# 2KbeaconDetectorV1_0.net
KiCad netlist of a schematic drawn in EAGLE
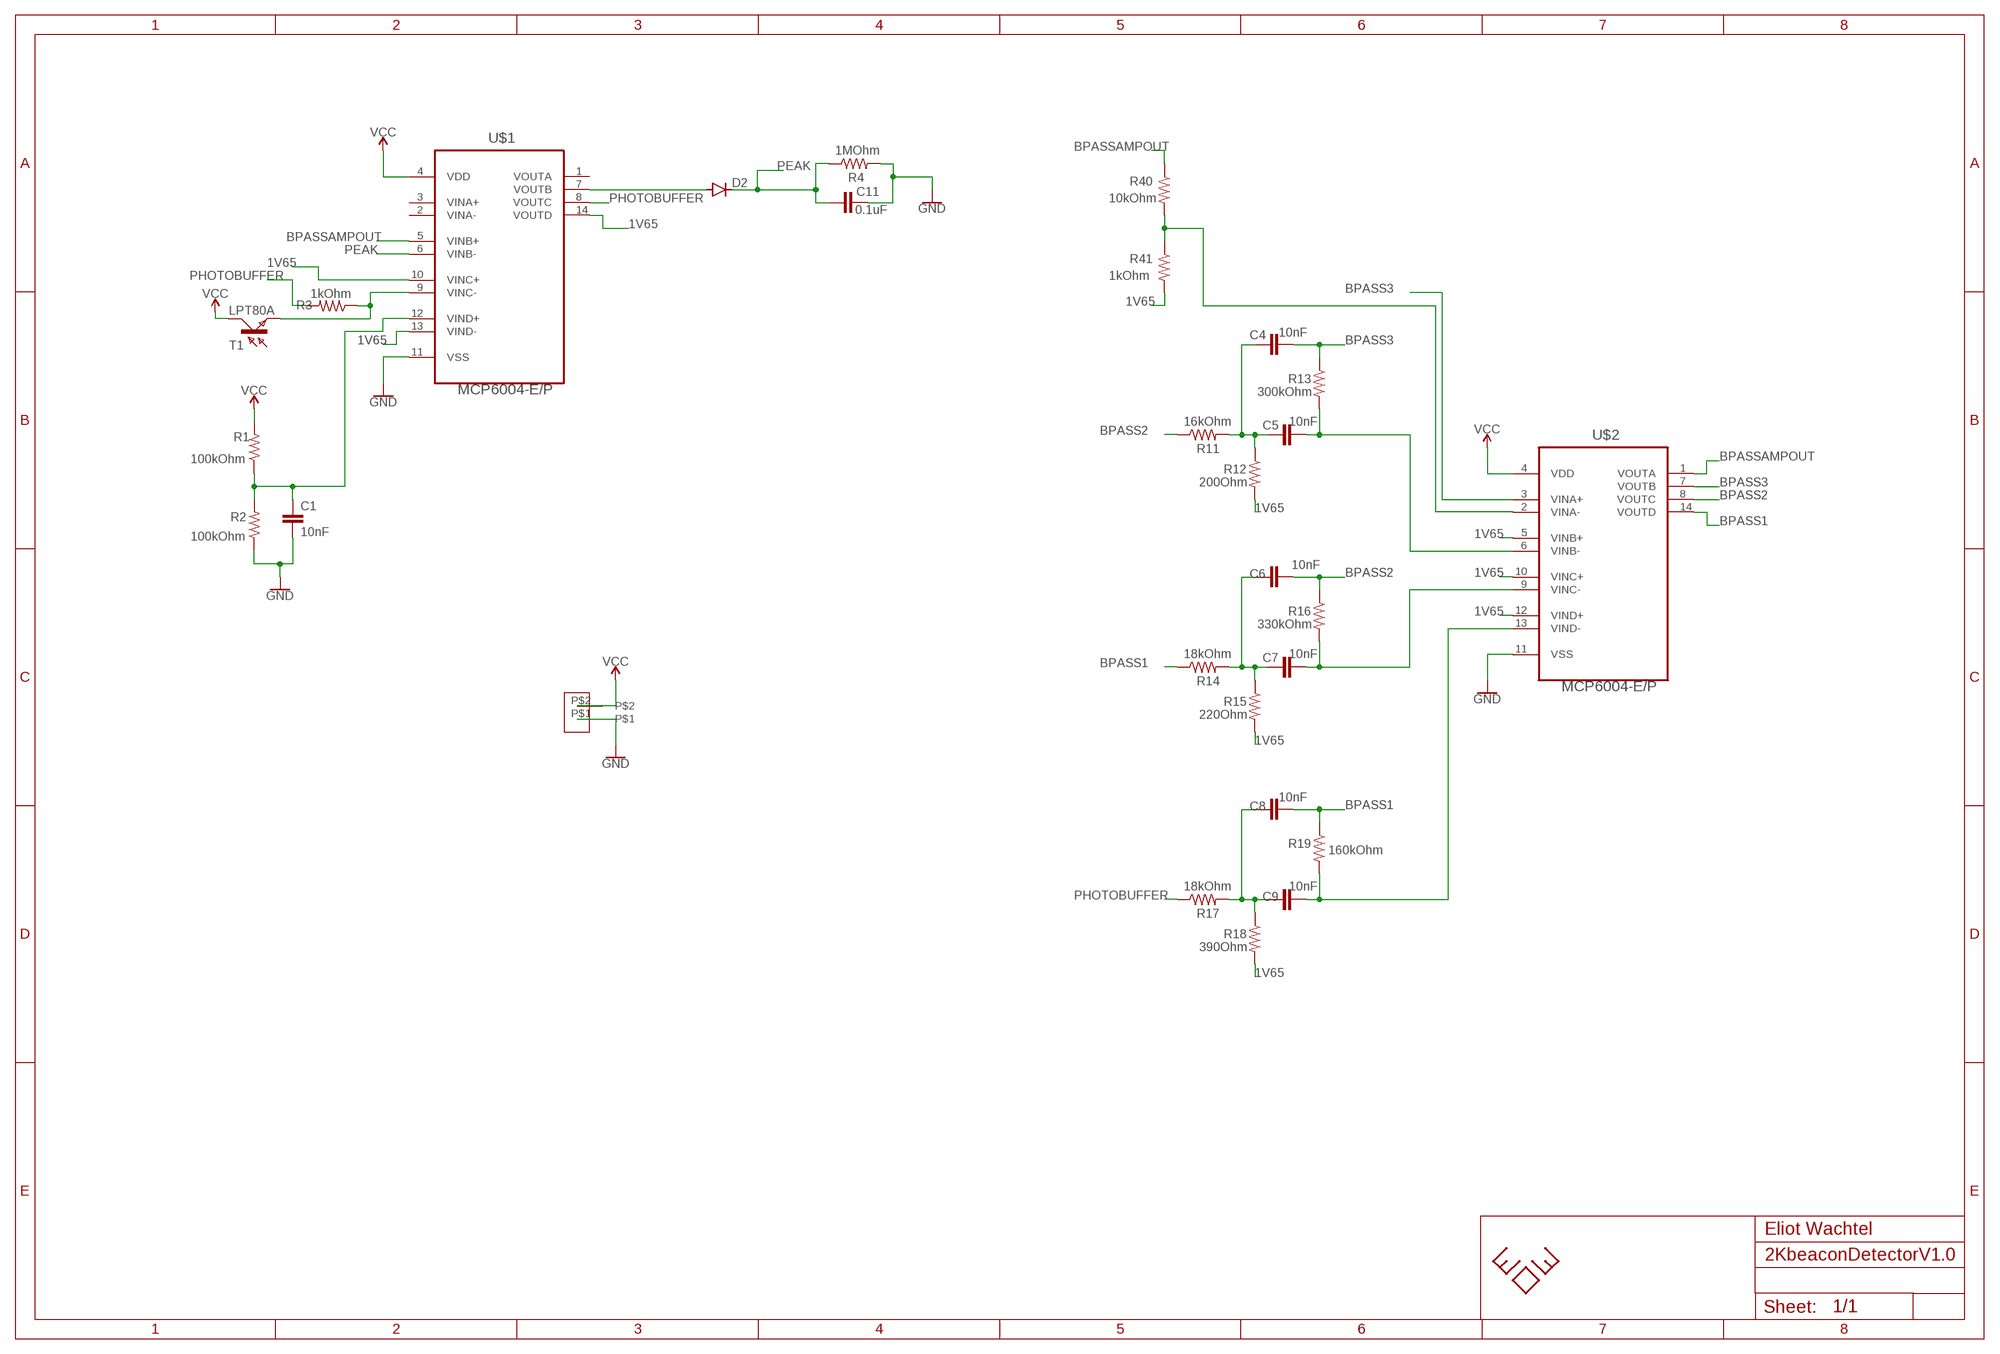
[diagram p0: schematic, sheet 1]

(export (version "E")
  (design (tool "Eeschema 10.0.6"))
  (components
    (comp (ref "C1")
      (value "10nF")
      (footprint "eagle-import:C5B2.5")
      (libsource (lib "eagle-import") (part "C5/2.5"))
    )
    (comp (ref "C4")
      (value "10nF")
      (footprint "eagle-import:C5B2.5")
      (libsource (lib "eagle-import") (part "C5/2.5"))
    )
    (comp (ref "C5")
      (value "10nF")
      (footprint "eagle-import:C5B2.5")
      (libsource (lib "eagle-import") (part "C5/2.5"))
    )
    (comp (ref "C6")
      (value "10nF")
      (footprint "eagle-import:C5B2.5")
      (libsource (lib "eagle-import") (part "C5/2.5"))
    )
    (comp (ref "C7")
      (value "10nF")
      (footprint "eagle-import:C5B2.5")
      (libsource (lib "eagle-import") (part "C5/2.5"))
    )
    (comp (ref "C8")
      (value "10nF")
      (footprint "eagle-import:C5B2.5")
      (libsource (lib "eagle-import") (part "C5/2.5"))
    )
    (comp (ref "C9")
      (value "10nF")
      (footprint "eagle-import:C5B2.5")
      (libsource (lib "eagle-import") (part "C5/2.5"))
    )
    (comp (ref "C11")
      (value "0.1uF")
      (footprint "eagle-import:C5B2.5")
      (libsource (lib "eagle-import") (part "C5/2.5"))
    )
    (comp (ref "D2")
      (value "DIODE-D-7.5")
      (footprint "eagle-import:D-7.5")
      (libsource (lib "eagle-import") (part "DIODE-D-7.5"))
    )
    (comp (ref "R1")
      (value "100kOhm")
      (footprint "eagle-import:0207_5V")
      (libsource (lib "eagle-import") (part "R-US_0207/5V"))
    )
    (comp (ref "R2")
      (value "100kOhm")
      (footprint "eagle-import:0207_5V")
      (libsource (lib "eagle-import") (part "R-US_0207/5V"))
    )
    (comp (ref "R3")
      (value "1kOhm")
      (footprint "eagle-import:0204V")
      (libsource (lib "eagle-import") (part "R-US_0204/2V"))
    )
    (comp (ref "R4")
      (value "1MOhm")
      (footprint "eagle-import:0204_5")
      (libsource (lib "eagle-import") (part "R-US_0204/5"))
    )
    (comp (ref "R11")
      (value "16kOhm")
      (footprint "eagle-import:0204V")
      (libsource (lib "eagle-import") (part "R-US_0204/2V"))
    )
    (comp (ref "R12")
      (value "200Ohm")
      (footprint "eagle-import:0204_7")
      (libsource (lib "eagle-import") (part "R-US_0204/7"))
    )
    (comp (ref "R13")
      (value "300kOhm")
      (footprint "eagle-import:0204V")
      (libsource (lib "eagle-import") (part "R-US_0204/2V"))
    )
    (comp (ref "R14")
      (value "18kOhm")
      (footprint "eagle-import:0204V")
      (libsource (lib "eagle-import") (part "R-US_0204/2V"))
    )
    (comp (ref "R15")
      (value "220Ohm")
      (footprint "eagle-import:0204_7")
      (libsource (lib "eagle-import") (part "R-US_0204/7"))
    )
    (comp (ref "R16")
      (value "330kOhm")
      (footprint "eagle-import:0204V")
      (libsource (lib "eagle-import") (part "R-US_0204/2V"))
    )
    (comp (ref "R17")
      (value "18kOhm")
      (footprint "eagle-import:0204V")
      (libsource (lib "eagle-import") (part "R-US_0204/2V"))
    )
    (comp (ref "R18")
      (value "390Ohm")
      (footprint "eagle-import:0204_7")
      (libsource (lib "eagle-import") (part "R-US_0204/7"))
    )
    (comp (ref "R19")
      (value "160kOhm")
      (footprint "eagle-import:0204V")
      (libsource (lib "eagle-import") (part "R-US_0204/2V"))
    )
    (comp (ref "R40")
      (value "10kOhm")
      (footprint "eagle-import:0204_7")
      (libsource (lib "eagle-import") (part "R-US_0204/7"))
    )
    (comp (ref "R41")
      (value "1kOhm")
      (footprint "eagle-import:0204_7")
      (libsource (lib "eagle-import") (part "R-US_0204/7"))
    )
    (comp (ref "T1")
      (value "LPT80A")
      (footprint "eagle-import:LPT80A")
      (libsource (lib "eagle-import") (part "LPT80A"))
    )
    (comp (ref "U$1")
      (value "MCP6004-E/P")
      (footprint "eagle-import:DIP254P762X533-14")
      (fields
        (field (name "DIGI-KEY_PART_NUMBER") "MCP6004-E/P-ND")
        (field (name "MF") "Microchip Technology")
      )
      (libsource (lib "eagle-import") (part "MCP6004-E/P"))
    )
    (comp (ref "U$2")
      (value "MCP6004-E/P")
      (footprint "eagle-import:DIP254P762X533-14")
      (fields
        (field (name "DIGI-KEY_PART_NUMBER") "MCP6004-E/P-ND")
        (field (name "MF") "Microchip Technology")
      )
      (libsource (lib "eagle-import") (part "MCP6004-E/P"))
    )
    (comp (ref "U$4")
      (value "WIRECONNECT2PIN")
      (footprint "eagle-import:WIRECONNECT2PIN")
      (libsource (lib "eagle-import") (part "WIRECONNECT2PIN"))
    )
  )
  (nets
    (net (code "1") (name "/1V65") (class "Default")
      (node (ref "R12") (pin "2") (pinfunction "2_2") (pintype "passive"))
      (node (ref "R15") (pin "2") (pinfunction "2_2") (pintype "passive"))
      (node (ref "R18") (pin "2") (pinfunction "2_2") (pintype "passive"))
      (node (ref "R41") (pin "2") (pinfunction "2_2") (pintype "passive"))
      (node (ref "U$1") (pin "10") (pinfunction "VINC+_10") (pintype "input"))
      (node (ref "U$1") (pin "13") (pinfunction "VIND-_13") (pintype "input"))
      (node (ref "U$1") (pin "14") (pinfunction "VOUTD_14") (pintype "output"))
      (node (ref "U$2") (pin "10") (pinfunction "VINC+_10") (pintype "input"))
      (node (ref "U$2") (pin "12") (pinfunction "VIND+_12") (pintype "input"))
      (node (ref "U$2") (pin "5") (pinfunction "VINB+_5") (pintype "input"))
    )
    (net (code "2") (name "/BPASS1") (class "Default")
      (node (ref "C8") (pin "2") (pinfunction "2_2") (pintype "passive"))
      (node (ref "R14") (pin "1") (pinfunction "1_1") (pintype "passive"))
      (node (ref "R19") (pin "1") (pinfunction "1_1") (pintype "passive"))
      (node (ref "U$2") (pin "14") (pinfunction "VOUTD_14") (pintype "output"))
    )
    (net (code "3") (name "/BPASS2") (class "Default")
      (node (ref "C6") (pin "2") (pinfunction "2_2") (pintype "passive"))
      (node (ref "R11") (pin "1") (pinfunction "1_1") (pintype "passive"))
      (node (ref "R16") (pin "1") (pinfunction "1_1") (pintype "passive"))
      (node (ref "U$2") (pin "8") (pinfunction "VOUTC_8") (pintype "output"))
    )
    (net (code "4") (name "/BPASS3") (class "Default")
      (node (ref "C4") (pin "2") (pinfunction "2_2") (pintype "passive"))
      (node (ref "R13") (pin "1") (pinfunction "1_1") (pintype "passive"))
      (node (ref "U$2") (pin "3") (pinfunction "VINA+_3") (pintype "input"))
      (node (ref "U$2") (pin "7") (pinfunction "VOUTB_7") (pintype "output"))
    )
    (net (code "5") (name "/BPASSAMPOUT") (class "Default")
      (node (ref "R40") (pin "1") (pinfunction "1_1") (pintype "passive"))
      (node (ref "U$1") (pin "5") (pinfunction "VINB+_5") (pintype "input"))
      (node (ref "U$2") (pin "1") (pinfunction "VOUTA_1") (pintype "output"))
    )
    (net (code "6") (name "/PEAK") (class "Default")
      (node (ref "C11") (pin "1") (pinfunction "1_1") (pintype "passive"))
      (node (ref "D2") (pin "C") (pinfunction "C_C") (pintype "passive"))
      (node (ref "R4") (pin "1") (pinfunction "1_1") (pintype "passive"))
      (node (ref "U$1") (pin "6") (pinfunction "VINB-_6") (pintype "input"))
    )
    (net (code "7") (name "/PHOTOBUFFER") (class "Default")
      (node (ref "R17") (pin "1") (pinfunction "1_1") (pintype "passive"))
      (node (ref "R3") (pin "2") (pinfunction "2_2") (pintype "passive"))
      (node (ref "U$1") (pin "8") (pinfunction "VOUTC_8") (pintype "output"))
    )
    (net (code "8") (name "GND") (class "Default")
      (node (ref "C1") (pin "2") (pinfunction "2_2") (pintype "passive"))
      (node (ref "C11") (pin "2") (pinfunction "2_2") (pintype "passive"))
      (node (ref "R2") (pin "1") (pinfunction "1_1") (pintype "passive"))
      (node (ref "R4") (pin "2") (pinfunction "2_2") (pintype "passive"))
      (node (ref "U$1") (pin "11") (pinfunction "VSS_11") (pintype "power_in"))
      (node (ref "U$2") (pin "11") (pinfunction "VSS_11") (pintype "power_in"))
      (node (ref "U$4") (pin "P$1") (pinfunction "P$1_P$1") (pintype "bidirectional"))
    )
    (net (code "9") (name "Net-(C4-Pad1)") (class "Default")
      (node (ref "C4") (pin "1") (pinfunction "1_1") (pintype "passive"))
      (node (ref "C5") (pin "1") (pinfunction "1_1") (pintype "passive"))
      (node (ref "R11") (pin "2") (pinfunction "2_2") (pintype "passive"))
      (node (ref "R12") (pin "1") (pinfunction "1_1") (pintype "passive"))
    )
    (net (code "10") (name "Net-(C6-Pad1)") (class "Default")
      (node (ref "C6") (pin "1") (pinfunction "1_1") (pintype "passive"))
      (node (ref "C7") (pin "1") (pinfunction "1_1") (pintype "passive"))
      (node (ref "R14") (pin "2") (pinfunction "2_2") (pintype "passive"))
      (node (ref "R15") (pin "1") (pinfunction "1_1") (pintype "passive"))
    )
    (net (code "11") (name "Net-(C8-Pad1)") (class "Default")
      (node (ref "C8") (pin "1") (pinfunction "1_1") (pintype "passive"))
      (node (ref "C9") (pin "1") (pinfunction "1_1") (pintype "passive"))
      (node (ref "R17") (pin "2") (pinfunction "2_2") (pintype "passive"))
      (node (ref "R18") (pin "1") (pinfunction "1_1") (pintype "passive"))
    )
    (net (code "12") (name "Net-(U$1-VINC-)") (class "Default")
      (node (ref "R3") (pin "1") (pinfunction "1_1") (pintype "passive"))
      (node (ref "T1") (pin "E") (pinfunction "E_E") (pintype "passive"))
      (node (ref "U$1") (pin "9") (pinfunction "VINC-_9") (pintype "input"))
    )
    (net (code "13") (name "Net-(U$1-VIND+)") (class "Default")
      (node (ref "C1") (pin "1") (pinfunction "1_1") (pintype "passive"))
      (node (ref "R1") (pin "1") (pinfunction "1_1") (pintype "passive"))
      (node (ref "R2") (pin "2") (pinfunction "2_2") (pintype "passive"))
      (node (ref "U$1") (pin "12") (pinfunction "VIND+_12") (pintype "input"))
    )
    (net (code "14") (name "Net-(U$1-VOUTB)") (class "Default")
      (node (ref "D2") (pin "A") (pinfunction "A_A") (pintype "passive"))
      (node (ref "U$1") (pin "7") (pinfunction "VOUTB_7") (pintype "output"))
    )
    (net (code "15") (name "Net-(U$2-VINA-)") (class "Default")
      (node (ref "R40") (pin "2") (pinfunction "2_2") (pintype "passive"))
      (node (ref "R41") (pin "1") (pinfunction "1_1") (pintype "passive"))
      (node (ref "U$2") (pin "2") (pinfunction "VINA-_2") (pintype "input"))
    )
    (net (code "16") (name "Net-(U$2-VINB-)") (class "Default")
      (node (ref "C5") (pin "2") (pinfunction "2_2") (pintype "passive"))
      (node (ref "R13") (pin "2") (pinfunction "2_2") (pintype "passive"))
      (node (ref "U$2") (pin "6") (pinfunction "VINB-_6") (pintype "input"))
    )
    (net (code "17") (name "Net-(U$2-VINC-)") (class "Default")
      (node (ref "C7") (pin "2") (pinfunction "2_2") (pintype "passive"))
      (node (ref "R16") (pin "2") (pinfunction "2_2") (pintype "passive"))
      (node (ref "U$2") (pin "9") (pinfunction "VINC-_9") (pintype "input"))
    )
    (net (code "18") (name "Net-(U$2-VIND-)") (class "Default")
      (node (ref "C9") (pin "2") (pinfunction "2_2") (pintype "passive"))
      (node (ref "R19") (pin "2") (pinfunction "2_2") (pintype "passive"))
      (node (ref "U$2") (pin "13") (pinfunction "VIND-_13") (pintype "input"))
    )
    (net (code "19") (name "VCC") (class "Default")
      (node (ref "R1") (pin "2") (pinfunction "2_2") (pintype "passive"))
      (node (ref "T1") (pin "C") (pinfunction "C_C") (pintype "passive"))
      (node (ref "U$1") (pin "4") (pinfunction "VDD_4") (pintype "power_in"))
      (node (ref "U$2") (pin "4") (pinfunction "VDD_4") (pintype "power_in"))
      (node (ref "U$4") (pin "P$2") (pinfunction "P$2_P$2") (pintype "bidirectional"))
    )
    (net (code "20") (name "unconnected-(U$1-VINA+-Pad3)") (class "Default")
      (node (ref "U$1") (pin "3") (pinfunction "VINA+_3") (pintype "input"))
    )
    (net (code "21") (name "unconnected-(U$1-VINA--Pad2)") (class "Default")
      (node (ref "U$1") (pin "2") (pinfunction "VINA-_2") (pintype "input"))
    )
    (net (code "22") (name "unconnected-(U$1-VOUTA-Pad1)") (class "Default")
      (node (ref "U$1") (pin "1") (pinfunction "VOUTA_1") (pintype "output"))
    )
  )
)
